# Sheet_tiny_dot.net
KiCad netlist of a schematic drawn in Altium Designer
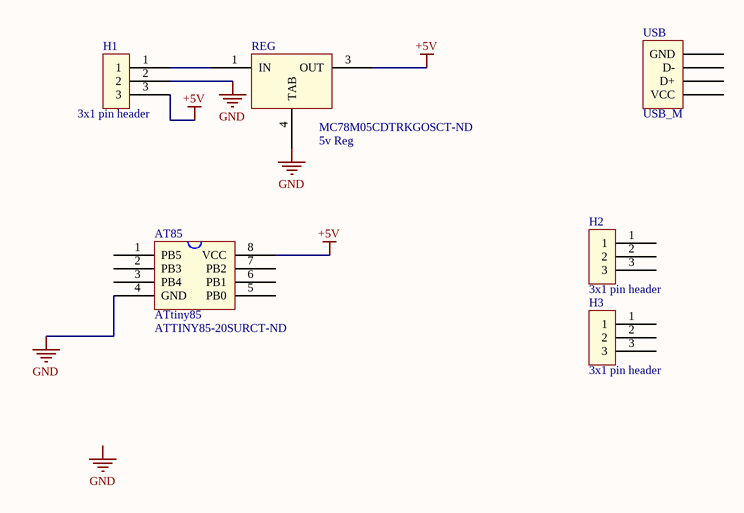
[diagram p0: Sheet_tiny_dot.SchDoc]

(export (version "E")
  (design (tool "Eeschema 10.0.6"))
  (components
    (comp (ref "AT85")
      (value "ATtiny85")
      (footprint "SOIC127P800X216-8N")
      (fields (field (name "SUPPLIER PART NUMBER 1") "ATTINY85-20SURCT-ND"))
      (libsource (lib "Schlib_tiny_dot") (part "ATtiny85"))
    )
    (comp (ref "H1")
      (value "3x1 pin header")
      (footprint "3x1 100mil header 1m diam")
      (libsource (lib "Schlib_tiny_dot") (part "3x1 pin header"))
    )
    (comp (ref "H2")
      (value "3x1 pin header")
      (footprint "3x1 100mil header 1m diam")
      (libsource (lib "Schlib_tiny_dot") (part "3x1 pin header"))
    )
    (comp (ref "H3")
      (value "3x1 pin header")
      (footprint "3x1 100mil header 1m diam")
      (libsource (lib "Schlib_tiny_dot") (part "3x1 pin header"))
    )
    (comp (ref "REG")
      (value "5v Reg")
      (fields (field (name "SUPPLIER PART NUMBER 1") "MC78M05CDTRKGOSCT-ND"))
      (libsource (lib "Schlib_tiny_dot") (part "5v Reg"))
    )
    (comp (ref "USB")
      (value "USB_M")
      (footprint "InlineUSB")
      (libsource (lib "Schlib_tiny_dot") (part "USB_M"))
    )
  )
  (nets
    (net (code "1") (name "+5V") (class "Default")
      (node (ref "AT85") (pin "8") (pinfunction "VCC_8") (pintype "passive"))
      (node (ref "H1") (pin "3") (pinfunction "3_3") (pintype "passive"))
      (node (ref "REG") (pin "3") (pinfunction "OUT_3") (pintype "passive"))
    )
    (net (code "2") (name "GND") (class "Default")
      (node (ref "AT85") (pin "4") (pinfunction "GND_4") (pintype "passive"))
      (node (ref "H1") (pin "2") (pinfunction "2_2") (pintype "passive"))
      (node (ref "REG") (pin "4") (pinfunction "TAB_4") (pintype "passive"))
    )
    (net (code "3") (name "Net-(REG-IN)") (class "Default")
      (node (ref "H1") (pin "1") (pinfunction "1_1") (pintype "passive"))
      (node (ref "REG") (pin "1") (pinfunction "IN_1") (pintype "passive"))
    )
    (net (code "4") (name "unconnected-(AT85-PB0-Pad5)") (class "Default")
      (node (ref "AT85") (pin "5") (pinfunction "PB0_5") (pintype "passive"))
    )
    (net (code "5") (name "unconnected-(AT85-PB1-Pad6)") (class "Default")
      (node (ref "AT85") (pin "6") (pinfunction "PB1_6") (pintype "passive"))
    )
    (net (code "6") (name "unconnected-(AT85-PB2-Pad7)") (class "Default")
      (node (ref "AT85") (pin "7") (pinfunction "PB2_7") (pintype "passive"))
    )
    (net (code "7") (name "unconnected-(AT85-PB3-Pad2)") (class "Default")
      (node (ref "AT85") (pin "2") (pinfunction "PB3_2") (pintype "passive"))
    )
    (net (code "8") (name "unconnected-(AT85-PB4-Pad3)") (class "Default")
      (node (ref "AT85") (pin "3") (pinfunction "PB4_3") (pintype "passive"))
    )
    (net (code "9") (name "unconnected-(AT85-PB5-Pad1)") (class "Default")
      (node (ref "AT85") (pin "1") (pinfunction "PB5_1") (pintype "passive"))
    )
    (net (code "10") (name "unconnected-(H2-Pad1)") (class "Default")
      (node (ref "H2") (pin "1") (pinfunction "1_1") (pintype "passive"))
    )
    (net (code "11") (name "unconnected-(H2-Pad2)") (class "Default")
      (node (ref "H2") (pin "2") (pinfunction "2_2") (pintype "passive"))
    )
    (net (code "12") (name "unconnected-(H2-Pad3)") (class "Default")
      (node (ref "H2") (pin "3") (pinfunction "3_3") (pintype "passive"))
    )
    (net (code "13") (name "unconnected-(H3-Pad1)") (class "Default")
      (node (ref "H3") (pin "1") (pinfunction "1_1") (pintype "passive"))
    )
    (net (code "14") (name "unconnected-(H3-Pad2)") (class "Default")
      (node (ref "H3") (pin "2") (pinfunction "2_2") (pintype "passive"))
    )
    (net (code "15") (name "unconnected-(H3-Pad3)") (class "Default")
      (node (ref "H3") (pin "3") (pinfunction "3_3") (pintype "passive"))
    )
    (net (code "16") (name "unconnected-(USB-PadD+)") (class "Default")
      (node (ref "USB") (pin "D+") (pinfunction "D+_D+") (pintype "passive"))
    )
    (net (code "17") (name "unconnected-(USB-PadD-)") (class "Default")
      (node (ref "USB") (pin "D-") (pinfunction "D-_D-") (pintype "passive"))
    )
    (net (code "18") (name "unconnected-(USB-PadGND)") (class "Default")
      (node (ref "USB") (pin "GND") (pinfunction "GND_GND") (pintype "passive"))
    )
    (net (code "19") (name "unconnected-(USB-PadVCC)") (class "Default")
      (node (ref "USB") (pin "VCC") (pinfunction "VCC_VCC") (pintype "passive"))
    )
  )
)
